# FLYBACK_SWITCHING_POWER_SUPPLY_V1_3.net
KiCad netlist of a schematic drawn in Altium Designer
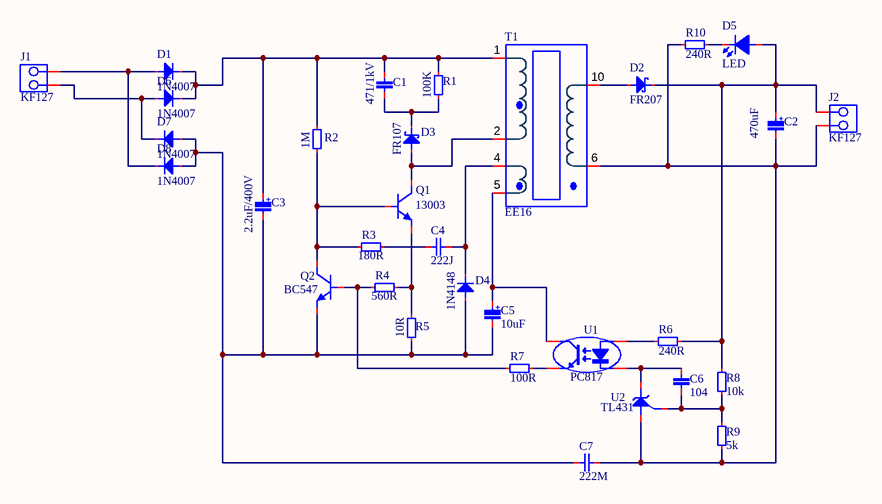
[diagram p0: FLYBACK_SWITCHING_POWER_SUPPLY_V1_3.SchDoc]

(export (version "E")
  (design (tool "Eeschema 10.0.6"))
  (components
    (comp (ref "C1")
      (value "471/1kV")
      (footprint "CAP_Ceramic_5MM")
      (libsource (lib "MyAltiumLibrary") (part "Capacitors(Disc)"))
    )
    (comp (ref "C2")
      (value "470uF")
      (footprint "CAP_RAD_D06.3x11")
      (libsource (lib "MyAltiumLibrary") (part "Capacitor(Radian)"))
    )
    (comp (ref "C3")
      (value "2.2uF/400V")
      (footprint "CAP_RAD_D10x12.5")
      (libsource (lib "MyAltiumLibrary") (part "Capacitor(Radian)"))
    )
    (comp (ref "C4")
      (value "222J")
      (footprint "CAP-FILM-5MM")
      (libsource (lib "MyAltiumLibrary") (part "Capacitors(film)"))
    )
    (comp (ref "C5")
      (value "10uF")
      (footprint "CAP_RAD_D05x11")
      (libsource (lib "MyAltiumLibrary") (part "Capacitor(Radian)"))
    )
    (comp (ref "C6")
      (value "104")
      (footprint "CAP_Ceramic_5MM")
      (libsource (lib "") (part "Capacitors(Disc)_2"))
    )
    (comp (ref "C7")
      (value "222M")
      (footprint "CAP_Ceramic_473M_9.65mm")
      (libsource (lib "") (part "Capacitors(Disc)_1"))
    )
    (comp (ref "D1")
      (value "1N4007")
      (footprint "DO-204AL-BK")
      (libsource (lib "MyAltiumLibrary") (part "Diode-1N4007"))
    )
    (comp (ref "D2")
      (value "FR207")
      (footprint "DO-204AC-BK")
      (libsource (lib "MyAltiumLibrary") (part "Diode-FR207"))
    )
    (comp (ref "D3")
      (value "FR107")
      (footprint "DO-204AL-BK")
      (description "1A 1000V")
      (libsource (lib "MyAltiumLibrary") (part "Diode-FR107"))
    )
    (comp (ref "D4")
      (value "1N4148")
      (footprint "DO-204AH-RD")
      (description "The fast switching diode")
      (libsource (lib "MyAltiumLibrary") (part "Diode-1N4148"))
    )
    (comp (ref "D5") (value "LED") (footprint "LED_5MM") (libsource (lib "MyAltiumLibrary") (part "LED 5MM")))
    (comp (ref "D6")
      (value "1N4007")
      (footprint "DO-204AL-BK")
      (libsource (lib "MyAltiumLibrary") (part "Diode-1N4007"))
    )
    (comp (ref "D7")
      (value "1N4007")
      (footprint "DO-204AL-BK")
      (libsource (lib "MyAltiumLibrary") (part "Diode-1N4007"))
    )
    (comp (ref "D8")
      (value "1N4007")
      (footprint "DO-204AL-BK")
      (libsource (lib "MyAltiumLibrary") (part "Diode-1N4007"))
    )
    (comp (ref "J1")
      (value "KF127")
      (footprint "DG127-5.0-02P-14-00AH")
      (libsource (lib "") (part "DG127-5.0-02P-14-00AH_1"))
    )
    (comp (ref "J2")
      (value "KF127")
      (footprint "DG127-5.0-02P-14-00AH")
      (libsource (lib "MyAltiumLibrary") (part "DG127-5.0-02P-14-00AH"))
    )
    (comp (ref "Q1")
      (value "13003")
      (footprint "TO-126")
      (libsource (lib "MyAltiumLibrary") (part "Transistor-MJE13003"))
    )
    (comp (ref "Q2")
      (value "BC547")
      (footprint "TO-92")
      (description "VCEO: 45 Vdc\r\nVCBO: 50 Vdc\r\nVEBO: 6.0 Vdc")
      (libsource (lib "MyAltiumLibrary") (part "Transistor-BC547"))
    )
    (comp (ref "R1") (value "100K") (footprint "RES-0.5W-H") (libsource (lib "") (part "Resistors THD_2")))
    (comp (ref "R2") (value "1M") (footprint "RES-0.25W-H") (libsource (lib "") (part "Resistors THD_2")))
    (comp (ref "R3")
      (value "180R")
      (footprint "RES-0.25W-H")
      (libsource (lib "MyAltiumLibrary") (part "Resistors THD"))
    )
    (comp (ref "R4")
      (value "560R")
      (footprint "RES-0.25W-H")
      (libsource (lib "MyAltiumLibrary") (part "Resistors THD"))
    )
    (comp (ref "R5") (value "10R") (footprint "RES-0.5W-V") (libsource (lib "") (part "Resistors THD_1")))
    (comp (ref "R6")
      (value "240R")
      (footprint "RES-0.25W-H")
      (libsource (lib "MyAltiumLibrary") (part "Resistors THD"))
    )
    (comp (ref "R7")
      (value "100R")
      (footprint "RES-0.25W-H")
      (libsource (lib "MyAltiumLibrary") (part "Resistors THD"))
    )
    (comp (ref "R8") (value "10k") (footprint "RES-0.25W-H") (libsource (lib "") (part "Resistors THD_1")))
    (comp (ref "R9") (value "5k") (footprint "RES-0.25W-H") (libsource (lib "") (part "Resistors THD_1")))
    (comp (ref "R10")
      (value "240R")
      (footprint "RES-0.25W-H")
      (libsource (lib "MyAltiumLibrary") (part "Resistors THD"))
    )
    (comp (ref "T1")
      (value "EE16")
      (footprint "TRANSFORMERS-EE16(5+5)-H")
      (libsource (lib "MyAltiumLibrary") (part "TRANS-EE16-HORIZONTAL(5+5)"))
    )
    (comp (ref "U1")
      (value "PC817")
      (footprint "PC817-DIP")
      (libsource (lib "MyAltiumLibrary") (part "Opto-PC817"))
    )
    (comp (ref "U2")
      (value "TL431")
      (footprint "TO-92")
      (libsource (lib "MyAltiumLibrary") (part "Ic-TL431"))
    )
  )
  (nets
    (net (code "1") (name "Net-(C1-Pad1)") (class "Default")
      (node (ref "C1") (pin "1") (pinfunction "1_1") (pintype "passive"))
      (node (ref "D3") (pin "2") (pinfunction "2_2") (pintype "passive"))
      (node (ref "R1") (pin "1") (pinfunction "1_1") (pintype "passive"))
    )
    (net (code "2") (name "Net-(C1-Pad2)") (class "Default")
      (node (ref "C1") (pin "2") (pinfunction "2_2") (pintype "passive"))
      (node (ref "C3") (pin "1") (pinfunction "1_1") (pintype "passive"))
      (node (ref "D1") (pin "2") (pinfunction "2_2") (pintype "passive"))
      (node (ref "D6") (pin "2") (pinfunction "2_2") (pintype "passive"))
      (node (ref "R1") (pin "2") (pinfunction "2_2") (pintype "passive"))
      (node (ref "R2") (pin "2") (pinfunction "2_2") (pintype "passive"))
      (node (ref "T1") (pin "1") (pinfunction "1_1") (pintype "passive"))
    )
    (net (code "3") (name "Net-(C2-Pad2)") (class "Default")
      (node (ref "C2") (pin "2") (pinfunction "2_2") (pintype "passive"))
      (node (ref "C7") (pin "2") (pinfunction "2_2") (pintype "passive"))
      (node (ref "J2") (pin "2") (pinfunction "2_2") (pintype "passive"))
      (node (ref "R10") (pin "2") (pinfunction "2_2") (pintype "passive"))
      (node (ref "R9") (pin "2") (pinfunction "2_2") (pintype "passive"))
      (node (ref "T1") (pin "6") (pinfunction "6_6") (pintype "passive"))
      (node (ref "U2") (pin "2") (pinfunction "2_2") (pintype "passive"))
    )
    (net (code "4") (name "Net-(C4-Pad1)") (class "Default")
      (node (ref "C4") (pin "1") (pinfunction "1_1") (pintype "passive"))
      (node (ref "R3") (pin "1") (pinfunction "1_1") (pintype "passive"))
    )
    (net (code "5") (name "Net-(C4-Pad2)") (class "Default")
      (node (ref "C4") (pin "2") (pinfunction "2_2") (pintype "passive"))
      (node (ref "D4") (pin "2") (pinfunction "2_2") (pintype "passive"))
      (node (ref "T1") (pin "4") (pinfunction "4_4") (pintype "passive"))
    )
    (net (code "6") (name "Net-(C6-Pad2)") (class "Default")
      (node (ref "C6") (pin "2") (pinfunction "2_2") (pintype "passive"))
      (node (ref "R8") (pin "2") (pinfunction "2_2") (pintype "passive"))
      (node (ref "R9") (pin "1") (pinfunction "1_1") (pintype "passive"))
      (node (ref "U2") (pin "1") (pinfunction "1_1") (pintype "passive"))
    )
    (net (code "7") (name "Net-(D1-Pad1)") (class "Default")
      (node (ref "D1") (pin "1") (pinfunction "1_1") (pintype "passive"))
      (node (ref "D8") (pin "2") (pinfunction "2_2") (pintype "passive"))
      (node (ref "J1") (pin "1") (pinfunction "1_1") (pintype "passive"))
    )
    (net (code "8") (name "Net-(D2-Pad1)") (class "Default")
      (node (ref "D2") (pin "1") (pinfunction "1_1") (pintype "passive"))
      (node (ref "T1") (pin "10") (pinfunction "10_10") (pintype "passive"))
    )
    (net (code "9") (name "Net-(D5-A)") (class "Default")
      (node (ref "C2") (pin "1") (pinfunction "1_1") (pintype "passive"))
      (node (ref "D2") (pin "2") (pinfunction "2_2") (pintype "passive"))
      (node (ref "D5") (pin "1") (pinfunction "A_1") (pintype "passive"))
      (node (ref "J2") (pin "1") (pinfunction "1_1") (pintype "passive"))
      (node (ref "R6") (pin "1") (pinfunction "1_1") (pintype "passive"))
      (node (ref "R8") (pin "1") (pinfunction "1_1") (pintype "passive"))
    )
    (net (code "10") (name "Net-(D5-K)") (class "Default")
      (node (ref "D5") (pin "2") (pinfunction "K_2") (pintype "passive"))
      (node (ref "R10") (pin "1") (pinfunction "1_1") (pintype "passive"))
    )
    (net (code "11") (name "Net-(D6-Pad1)") (class "Default")
      (node (ref "D6") (pin "1") (pinfunction "1_1") (pintype "passive"))
      (node (ref "D7") (pin "2") (pinfunction "2_2") (pintype "passive"))
      (node (ref "J1") (pin "2") (pinfunction "2_2") (pintype "passive"))
    )
    (net (code "12") (name "Net-(Q1-B)") (class "Default")
      (node (ref "Q1") (pin "1") (pinfunction "B_1") (pintype "passive"))
      (node (ref "Q2") (pin "1") (pinfunction "C_1") (pintype "passive"))
      (node (ref "R2") (pin "1") (pinfunction "1_1") (pintype "passive"))
      (node (ref "R3") (pin "2") (pinfunction "2_2") (pintype "passive"))
    )
    (net (code "13") (name "Net-(Q1-C)") (class "Default")
      (node (ref "D3") (pin "1") (pinfunction "1_1") (pintype "passive"))
      (node (ref "Q1") (pin "2") (pinfunction "C_2") (pintype "passive"))
      (node (ref "T1") (pin "2") (pinfunction "2_2") (pintype "passive"))
    )
    (net (code "14") (name "Net-(Q1-E)") (class "Default")
      (node (ref "Q1") (pin "3") (pinfunction "E_3") (pintype "passive"))
      (node (ref "R4") (pin "1") (pinfunction "1_1") (pintype "passive"))
      (node (ref "R5") (pin "1") (pinfunction "1_1") (pintype "passive"))
    )
    (net (code "15") (name "Net-(Q2-B)") (class "Default")
      (node (ref "Q2") (pin "2") (pinfunction "B_2") (pintype "passive"))
      (node (ref "R4") (pin "2") (pinfunction "2_2") (pintype "passive"))
      (node (ref "R7") (pin "2") (pinfunction "2_2") (pintype "passive"))
    )
    (net (code "16") (name "Net-(Q2-E)") (class "Default")
      (node (ref "C3") (pin "2") (pinfunction "2_2") (pintype "passive"))
      (node (ref "C5") (pin "2") (pinfunction "2_2") (pintype "passive"))
      (node (ref "C7") (pin "1") (pinfunction "1_1") (pintype "passive"))
      (node (ref "D4") (pin "1") (pinfunction "1_1") (pintype "passive"))
      (node (ref "D7") (pin "1") (pinfunction "1_1") (pintype "passive"))
      (node (ref "D8") (pin "1") (pinfunction "1_1") (pintype "passive"))
      (node (ref "Q2") (pin "3") (pinfunction "E_3") (pintype "passive"))
      (node (ref "R5") (pin "2") (pinfunction "2_2") (pintype "passive"))
    )
    (net (code "17") (name "Net-(U1-A)") (class "Default")
      (node (ref "R6") (pin "2") (pinfunction "2_2") (pintype "passive"))
      (node (ref "U1") (pin "1") (pinfunction "A_1") (pintype "passive"))
    )
    (net (code "18") (name "Net-(U1-C)") (class "Default")
      (node (ref "C5") (pin "1") (pinfunction "1_1") (pintype "passive"))
      (node (ref "T1") (pin "5") (pinfunction "5_5") (pintype "passive"))
      (node (ref "U1") (pin "4") (pinfunction "C_4") (pintype "passive"))
    )
    (net (code "19") (name "Net-(U1-E)") (class "Default")
      (node (ref "R7") (pin "1") (pinfunction "1_1") (pintype "passive"))
      (node (ref "U1") (pin "3") (pinfunction "E_3") (pintype "passive"))
    )
    (net (code "20") (name "Net-(U1-K)") (class "Default")
      (node (ref "C6") (pin "1") (pinfunction "1_1") (pintype "passive"))
      (node (ref "U1") (pin "2") (pinfunction "K_2") (pintype "passive"))
      (node (ref "U2") (pin "3") (pinfunction "3_3") (pintype "passive"))
    )
  )
)
